# ProPinEZMachBAutoRouteV2c.net
KiCad netlist of a schematic drawn in EAGLE
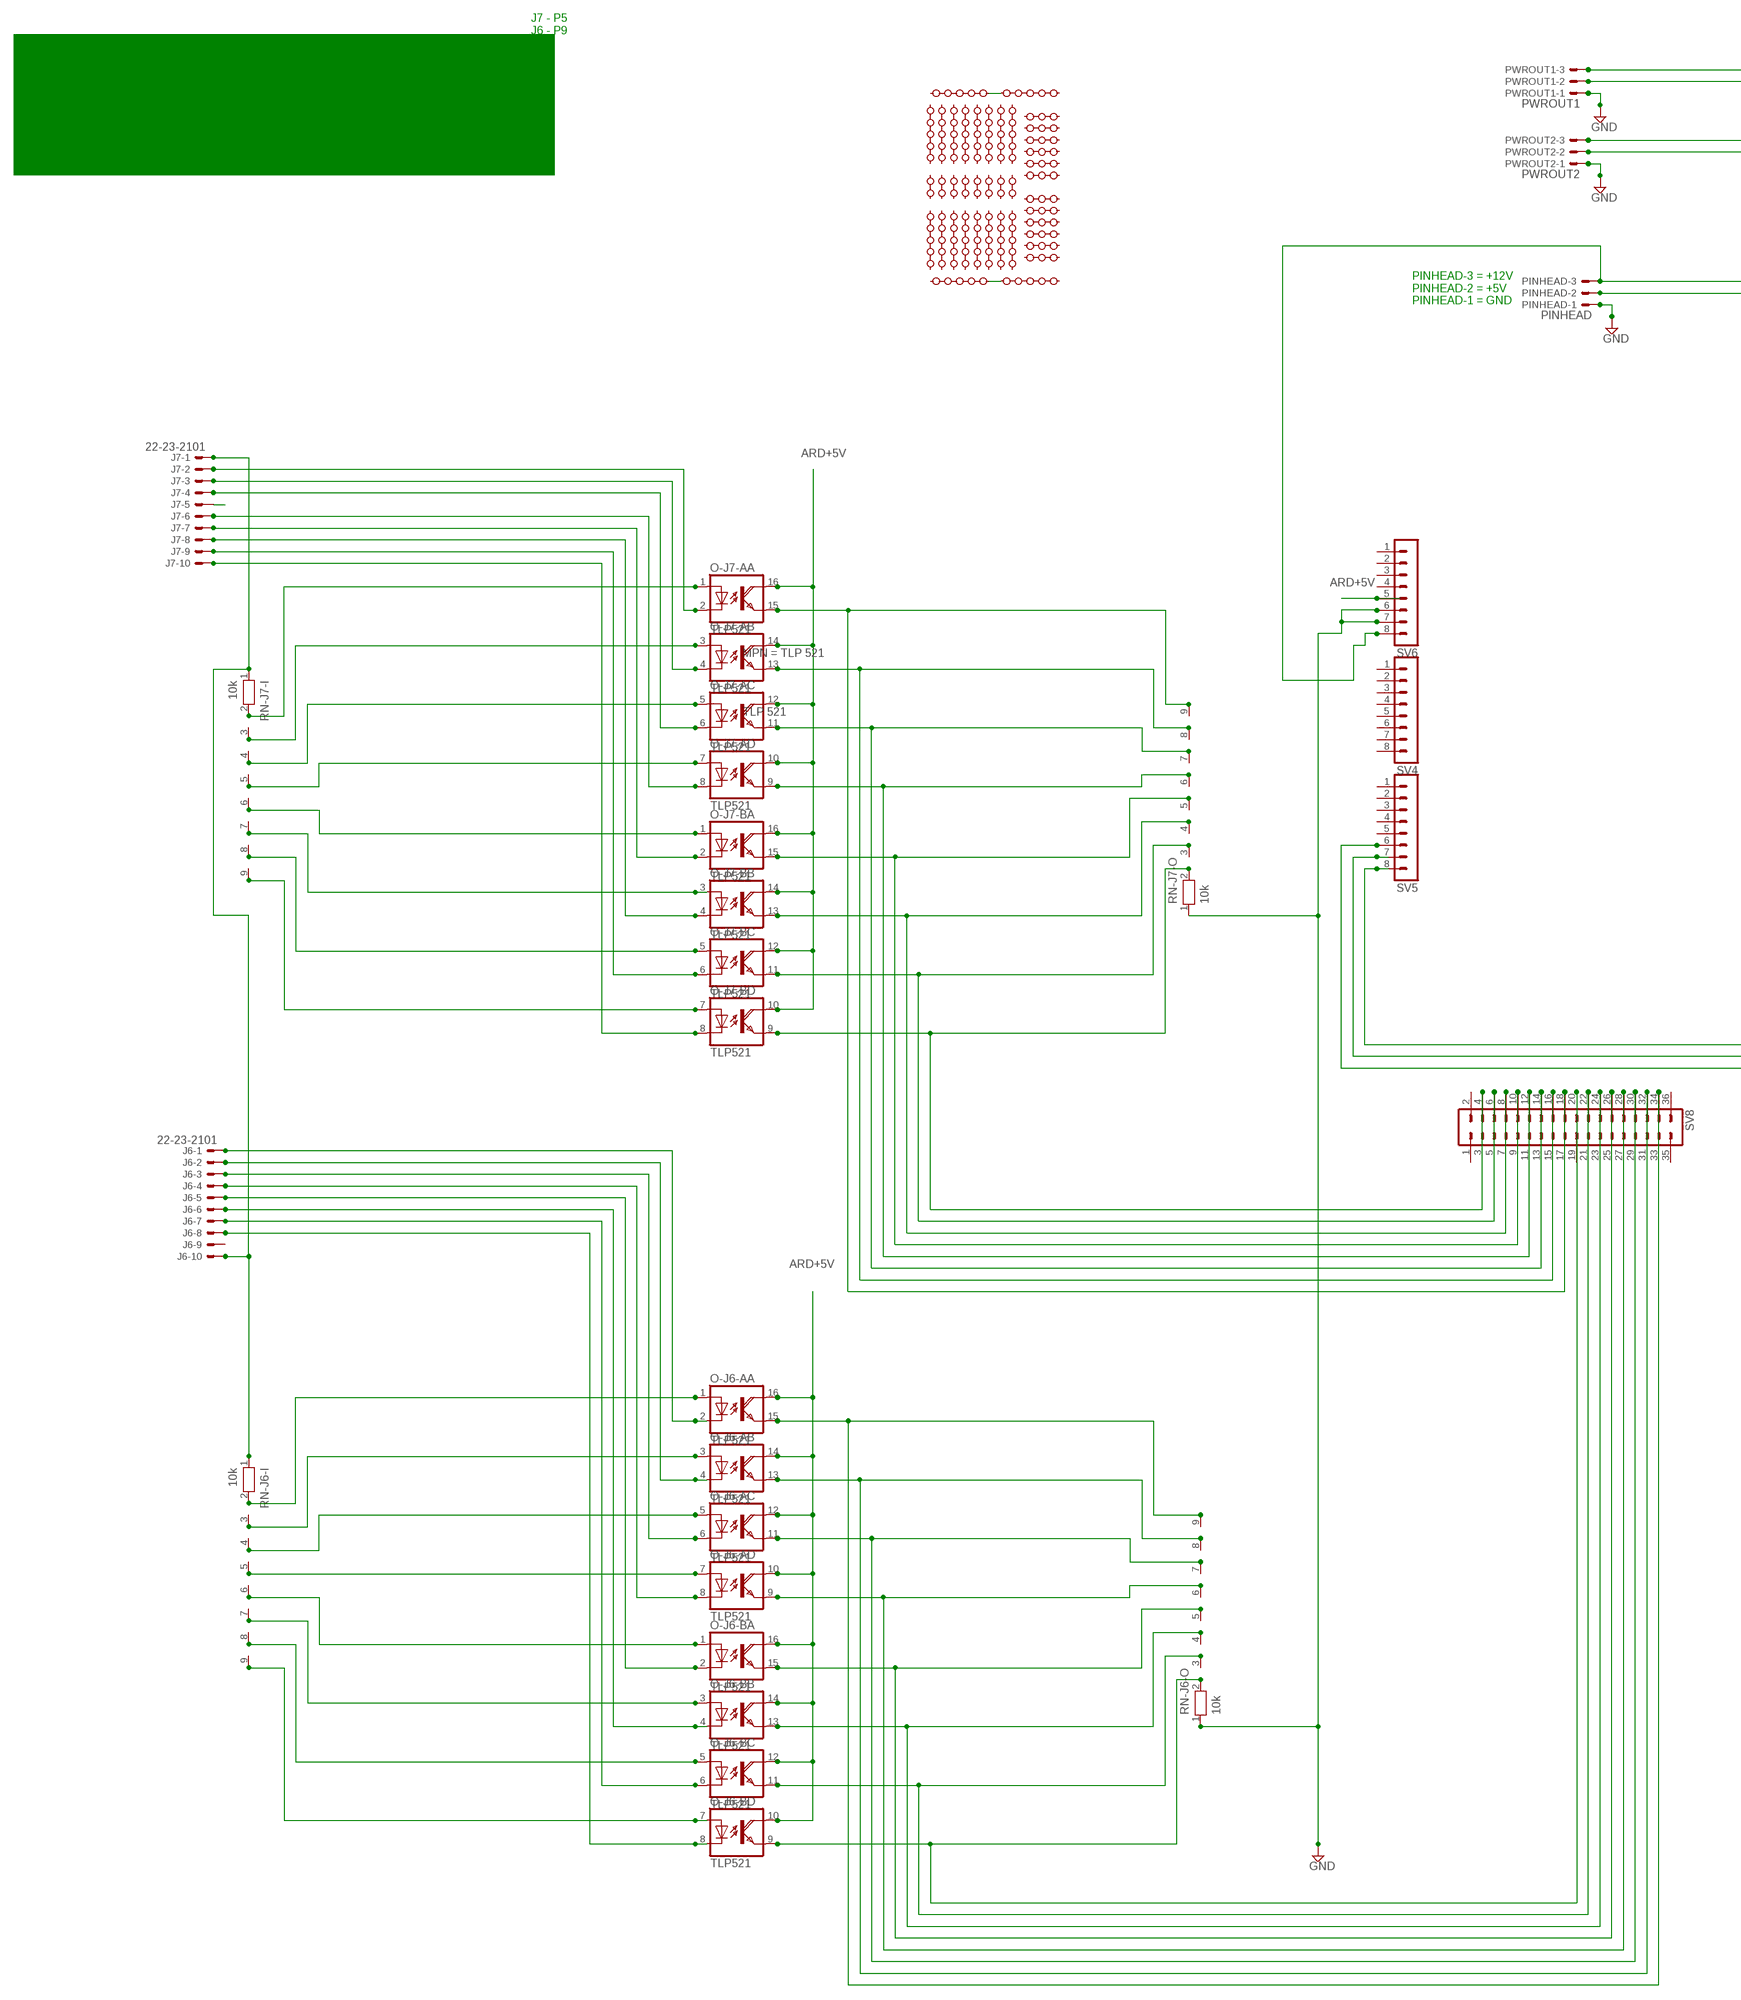
[diagram p0: schematic, sheet 1, part 1 of 2]
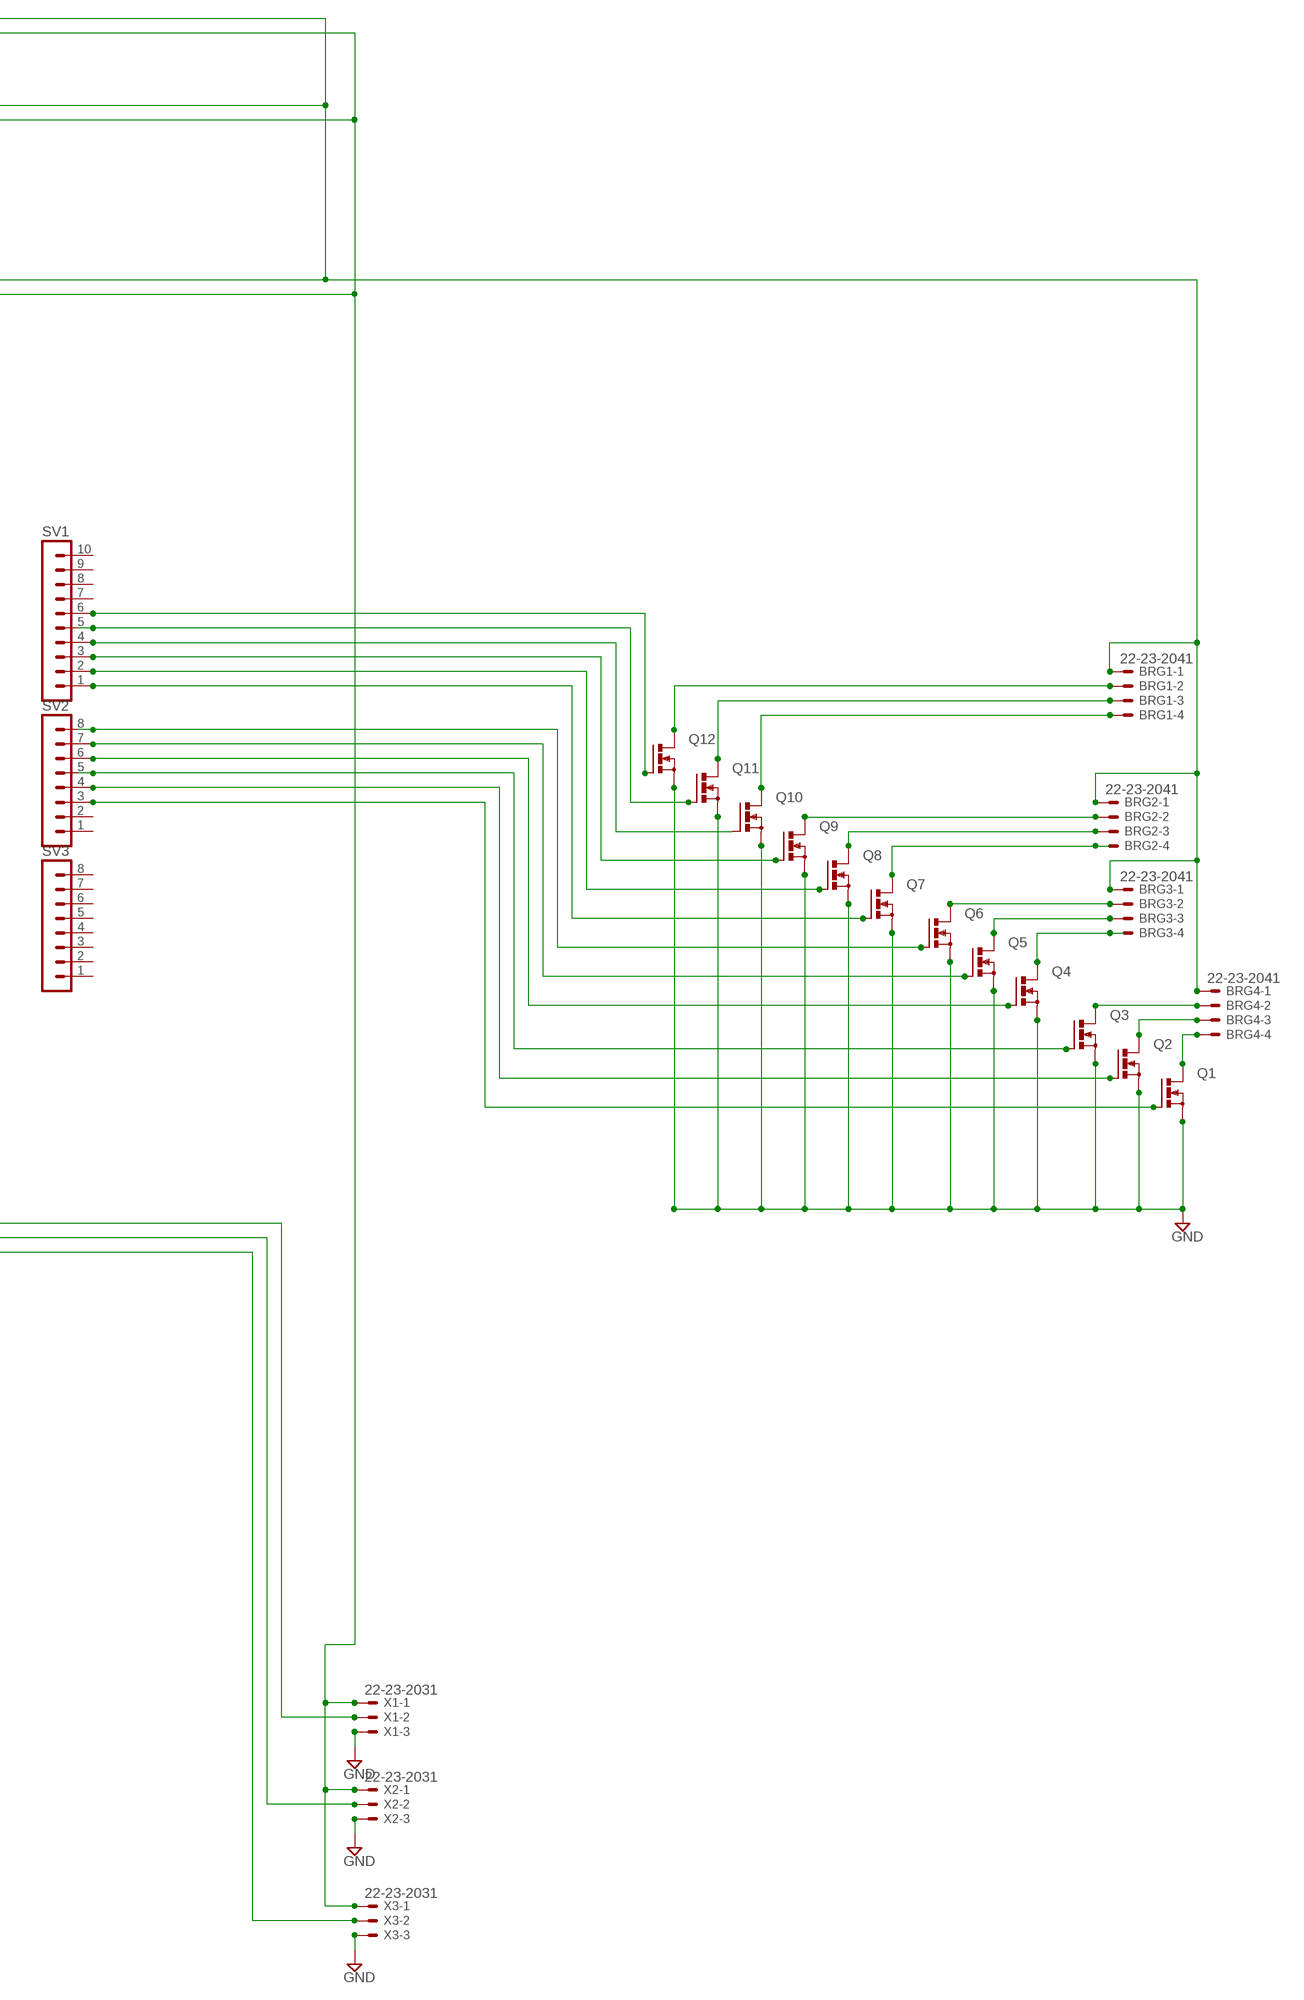
[diagram p1: schematic, sheet 1, part 2 of 2]

(export (version "E")
  (design (tool "Eeschema 10.0.6"))
  (components
    (comp (ref "BRG1")
      (value "22-23-2041")
      (footprint "eagle-import:22-23-2041")
      (fields (field (name "MF") "MOLEX"))
      (libsource (lib "eagle-import") (part "22-23-2041"))
    )
    (comp (ref "BRG2")
      (value "22-23-2041")
      (footprint "eagle-import:22-23-2041")
      (fields (field (name "MF") "MOLEX"))
      (libsource (lib "eagle-import") (part "22-23-2041"))
    )
    (comp (ref "BRG3")
      (value "22-23-2041")
      (footprint "eagle-import:22-23-2041")
      (fields (field (name "MF") "MOLEX"))
      (libsource (lib "eagle-import") (part "22-23-2041"))
    )
    (comp (ref "BRG4")
      (value "22-23-2041")
      (footprint "eagle-import:22-23-2041")
      (fields (field (name "MF") "MOLEX"))
      (libsource (lib "eagle-import") (part "22-23-2041"))
    )
    (comp (ref "J6")
      (value "22-23-2101")
      (footprint "eagle-import:22-23-2101")
      (fields (field (name "MF") "MOLEX"))
      (libsource (lib "eagle-import") (part "22-23-2101"))
    )
    (comp (ref "J7")
      (value "22-23-2101")
      (footprint "eagle-import:22-23-2101")
      (fields (field (name "MF") "MOLEX"))
      (libsource (lib "eagle-import") (part "22-23-2101"))
    )
    (comp (ref "O-J6-A")
      (value "TLP521")
      (footprint "eagle-import:DIL16")
      (fields (field (name "MPN") "TIL 199"))
      (libsource (lib "eagle-import") (part "TIL199"))
    )
    (comp (ref "O-J6-B")
      (value "TLP521")
      (footprint "eagle-import:DIL16")
      (fields (field (name "MPN") "TIL 199"))
      (libsource (lib "eagle-import") (part "TIL199"))
    )
    (comp (ref "O-J7-A")
      (value "TLP521")
      (footprint "eagle-import:DIL16")
      (fields (field (name "MPN") "TIL 199") (field (name "MPN_1") "TLP 521"))
      (libsource (lib "eagle-import") (part "TIL199"))
    )
    (comp (ref "O-J7-B")
      (value "TLP521")
      (footprint "eagle-import:DIL16")
      (fields (field (name "MPN") "TIL 199"))
      (libsource (lib "eagle-import") (part "TIL199"))
    )
    (comp (ref "P1")
      (value "PADSTRIP5-HA")
      (footprint "eagle-import:PADSTRIP-5H")
      (libsource (lib "eagle-import") (part "PADSTRIP5-HA"))
    )
    (comp (ref "P2")
      (value "PADSTRIP5-HA")
      (footprint "eagle-import:PADSTRIP-5H")
      (libsource (lib "eagle-import") (part "PADSTRIP5-HA"))
    )
    (comp (ref "P3")
      (value "PADSTRIP5-HA")
      (footprint "eagle-import:PADSTRIP-5H")
      (libsource (lib "eagle-import") (part "PADSTRIP5-HA"))
    )
    (comp (ref "P4")
      (value "PADSTRIP5-HA")
      (footprint "eagle-import:PADSTRIP-5H")
      (libsource (lib "eagle-import") (part "PADSTRIP5-HA"))
    )
    (comp (ref "P5")
      (value "PADSTRIP5-HA")
      (footprint "eagle-import:PADSTRIP-5H")
      (libsource (lib "eagle-import") (part "PADSTRIP5-HA"))
    )
    (comp (ref "P6")
      (value "PADSTRIP5-HA")
      (footprint "eagle-import:PADSTRIP-5H")
      (libsource (lib "eagle-import") (part "PADSTRIP5-HA"))
    )
    (comp (ref "P7")
      (value "PADSTRIP5-HA")
      (footprint "eagle-import:PADSTRIP-5H")
      (libsource (lib "eagle-import") (part "PADSTRIP5-HA"))
    )
    (comp (ref "P8")
      (value "PADSTRIP5-HA")
      (footprint "eagle-import:PADSTRIP-5H")
      (libsource (lib "eagle-import") (part "PADSTRIP5-HA"))
    )
    (comp (ref "P9")
      (value "PADSTRIP5-HA")
      (footprint "eagle-import:PADSTRIP-5H")
      (libsource (lib "eagle-import") (part "PADSTRIP5-HA"))
    )
    (comp (ref "P10")
      (value "PADSTRIP5-HA")
      (footprint "eagle-import:PADSTRIP-5H")
      (libsource (lib "eagle-import") (part "PADSTRIP5-HA"))
    )
    (comp (ref "P11")
      (value "PADSTRIP5-HA")
      (footprint "eagle-import:PADSTRIP-5H")
      (libsource (lib "eagle-import") (part "PADSTRIP5-HA"))
    )
    (comp (ref "P12")
      (value "PADSTRIP5-HA")
      (footprint "eagle-import:PADSTRIP-5H")
      (libsource (lib "eagle-import") (part "PADSTRIP5-HA"))
    )
    (comp (ref "P13")
      (value "PADSTRIP5-HA")
      (footprint "eagle-import:PADSTRIP-5H")
      (libsource (lib "eagle-import") (part "PADSTRIP5-HA"))
    )
    (comp (ref "P14")
      (value "PADSTRIP5-HA")
      (footprint "eagle-import:PADSTRIP-5H")
      (libsource (lib "eagle-import") (part "PADSTRIP5-HA"))
    )
    (comp (ref "P15")
      (value "PADSTRIP5-HA")
      (footprint "eagle-import:PADSTRIP-5H")
      (libsource (lib "eagle-import") (part "PADSTRIP5-HA"))
    )
    (comp (ref "P16")
      (value "PADSTRIP5-HA")
      (footprint "eagle-import:PADSTRIP-5H")
      (libsource (lib "eagle-import") (part "PADSTRIP5-HA"))
    )
    (comp (ref "P17")
      (value "PADSTRIP5-HB")
      (footprint "eagle-import:PADSTRIP-5HC")
      (libsource (lib "eagle-import") (part "PADSTRIP5-HB"))
    )
    (comp (ref "P18")
      (value "PADSTRIP5-HB")
      (footprint "eagle-import:PADSTRIP-5HC")
      (libsource (lib "eagle-import") (part "PADSTRIP5-HB"))
    )
    (comp (ref "P19")
      (value "PADSTRIP5-HB")
      (footprint "eagle-import:PADSTRIP-5HC")
      (libsource (lib "eagle-import") (part "PADSTRIP5-HB"))
    )
    (comp (ref "P20")
      (value "PADSTRIP5-HB")
      (footprint "eagle-import:PADSTRIP-5HC")
      (libsource (lib "eagle-import") (part "PADSTRIP5-HB"))
    )
    (comp (ref "PINHEAD")
      (value "PINHEAD")
      (footprint "eagle-import:22-23-2031")
      (fields (field (name "MF") "MOLEX") (field (name "MPN") "22-23-2031"))
      (libsource (lib "eagle-import") (part "22-23-2031"))
    )
    (comp (ref "PR1")
      (value "PADSTRIP3-H")
      (footprint "eagle-import:PADSTRIP-3H")
      (libsource (lib "eagle-import") (part "PADSTRIP3-H"))
    )
    (comp (ref "PR2")
      (value "PADSTRIP3-H")
      (footprint "eagle-import:PADSTRIP-3H")
      (libsource (lib "eagle-import") (part "PADSTRIP3-H"))
    )
    (comp (ref "PR3")
      (value "PADSTRIP3-H")
      (footprint "eagle-import:PADSTRIP-3H")
      (libsource (lib "eagle-import") (part "PADSTRIP3-H"))
    )
    (comp (ref "PR4")
      (value "PADSTRIP3-H")
      (footprint "eagle-import:PADSTRIP-3H")
      (libsource (lib "eagle-import") (part "PADSTRIP3-H"))
    )
    (comp (ref "PR5")
      (value "PADSTRIP3-H")
      (footprint "eagle-import:PADSTRIP-3H")
      (libsource (lib "eagle-import") (part "PADSTRIP3-H"))
    )
    (comp (ref "PR6")
      (value "PADSTRIP3-H")
      (footprint "eagle-import:PADSTRIP-3H")
      (libsource (lib "eagle-import") (part "PADSTRIP3-H"))
    )
    (comp (ref "PR7")
      (value "PADSTRIP3-H")
      (footprint "eagle-import:PADSTRIP-3H")
      (libsource (lib "eagle-import") (part "PADSTRIP3-H"))
    )
    (comp (ref "PR8")
      (value "PADSTRIP3-H")
      (footprint "eagle-import:PADSTRIP-3H")
      (libsource (lib "eagle-import") (part "PADSTRIP3-H"))
    )
    (comp (ref "PR9")
      (value "PADSTRIP3-H")
      (footprint "eagle-import:PADSTRIP-3H")
      (libsource (lib "eagle-import") (part "PADSTRIP3-H"))
    )
    (comp (ref "PR10")
      (value "PADSTRIP3-H")
      (footprint "eagle-import:PADSTRIP-3H")
      (libsource (lib "eagle-import") (part "PADSTRIP3-H"))
    )
    (comp (ref "PR13")
      (value "PADSTRIP2-H")
      (footprint "eagle-import:PADSTRIP-2H")
      (libsource (lib "eagle-import") (part "PADSTRIP2-H"))
    )
    (comp (ref "PR14")
      (value "PADSTRIP2-H")
      (footprint "eagle-import:PADSTRIP-2H")
      (libsource (lib "eagle-import") (part "PADSTRIP2-H"))
    )
    (comp (ref "PR15")
      (value "PADSTRIP2-H")
      (footprint "eagle-import:PADSTRIP-2H")
      (libsource (lib "eagle-import") (part "PADSTRIP2-H"))
    )
    (comp (ref "PR16")
      (value "PADSTRIP2-H")
      (footprint "eagle-import:PADSTRIP-2H")
      (libsource (lib "eagle-import") (part "PADSTRIP2-H"))
    )
    (comp (ref "PR17")
      (value "PADSTRIP2-H")
      (footprint "eagle-import:PADSTRIP-2H")
      (libsource (lib "eagle-import") (part "PADSTRIP2-H"))
    )
    (comp (ref "PR18")
      (value "PADSTRIP2-H")
      (footprint "eagle-import:PADSTRIP-2H")
      (libsource (lib "eagle-import") (part "PADSTRIP2-H"))
    )
    (comp (ref "PR19")
      (value "PADSTRIP2-H")
      (footprint "eagle-import:PADSTRIP-2H")
      (libsource (lib "eagle-import") (part "PADSTRIP2-H"))
    )
    (comp (ref "PR20")
      (value "PADSTRIP2-H")
      (footprint "eagle-import:PADSTRIP-2H")
      (libsource (lib "eagle-import") (part "PADSTRIP2-H"))
    )
    (comp (ref "PR23")
      (value "PADSTRIP3-H")
      (footprint "eagle-import:PADSTRIP-3H")
      (libsource (lib "eagle-import") (part "PADSTRIP3-H"))
    )
    (comp (ref "PR24")
      (value "PADSTRIP3-H")
      (footprint "eagle-import:PADSTRIP-3H")
      (libsource (lib "eagle-import") (part "PADSTRIP3-H"))
    )
    (comp (ref "PWROUT1")
      (value "PWROUT1")
      (footprint "eagle-import:22-23-2031")
      (fields (field (name "MF") "MOLEX") (field (name "MPN") "22-23-2031"))
      (libsource (lib "eagle-import") (part "22-23-2031"))
    )
    (comp (ref "PWROUT2")
      (value "PWROUT2")
      (footprint "eagle-import:22-23-2031")
      (fields (field (name "MF") "MOLEX") (field (name "MPN") "22-23-2031"))
      (libsource (lib "eagle-import") (part "22-23-2031"))
    )
    (comp (ref "Q1")
      (value "PMOSFET_NTO220BV")
      (footprint "eagle-import:TO220BV")
      (libsource (lib "eagle-import") (part "PMOSFET_NTO220BV"))
    )
    (comp (ref "Q2")
      (value "PMOSFET_NTO220BV")
      (footprint "eagle-import:TO220BV")
      (libsource (lib "eagle-import") (part "PMOSFET_NTO220BV"))
    )
    (comp (ref "Q3")
      (value "PMOSFET_NTO220BV")
      (footprint "eagle-import:TO220BV")
      (libsource (lib "eagle-import") (part "PMOSFET_NTO220BV"))
    )
    (comp (ref "Q4")
      (value "PMOSFET_NTO220BV")
      (footprint "eagle-import:TO220BV")
      (libsource (lib "eagle-import") (part "PMOSFET_NTO220BV"))
    )
    (comp (ref "Q5")
      (value "PMOSFET_NTO220BV")
      (footprint "eagle-import:TO220BV")
      (libsource (lib "eagle-import") (part "PMOSFET_NTO220BV"))
    )
    (comp (ref "Q6")
      (value "PMOSFET_NTO220BV")
      (footprint "eagle-import:TO220BV")
      (libsource (lib "eagle-import") (part "PMOSFET_NTO220BV"))
    )
    (comp (ref "Q7")
      (value "PMOSFET_NTO220BV")
      (footprint "eagle-import:TO220BV")
      (libsource (lib "eagle-import") (part "PMOSFET_NTO220BV"))
    )
    (comp (ref "Q8")
      (value "PMOSFET_NTO220BV")
      (footprint "eagle-import:TO220BV")
      (libsource (lib "eagle-import") (part "PMOSFET_NTO220BV"))
    )
    (comp (ref "Q9")
      (value "PMOSFET_NTO220BV")
      (footprint "eagle-import:TO220BV")
      (libsource (lib "eagle-import") (part "PMOSFET_NTO220BV"))
    )
    (comp (ref "Q10")
      (value "PMOSFET_NTO220BV")
      (footprint "eagle-import:TO220BV")
      (libsource (lib "eagle-import") (part "PMOSFET_NTO220BV"))
    )
    (comp (ref "Q11")
      (value "PMOSFET_NTO220BV")
      (footprint "eagle-import:TO220BV")
      (libsource (lib "eagle-import") (part "PMOSFET_NTO220BV"))
    )
    (comp (ref "Q12")
      (value "PMOSFET_NTO220BV")
      (footprint "eagle-import:TO220BV")
      (libsource (lib "eagle-import") (part "PMOSFET_NTO220BV"))
    )
    (comp (ref "RN-J6-I")
      (value "10k")
      (footprint "eagle-import:RN-9")
      (libsource (lib "eagle-import") (part "RN08"))
    )
    (comp (ref "RN-J6-O")
      (value "10k")
      (footprint "eagle-import:RN-9")
      (libsource (lib "eagle-import") (part "RN08"))
    )
    (comp (ref "RN-J7-I")
      (value "10k")
      (footprint "eagle-import:RN-9")
      (libsource (lib "eagle-import") (part "RN08"))
    )
    (comp (ref "RN-J7-O")
      (value "10k")
      (footprint "eagle-import:RN-9")
      (libsource (lib "eagle-import") (part "RN08"))
    )
    (comp (ref "SV1")
      (value "MA10-1")
      (footprint "eagle-import:MA10-1")
      (libsource (lib "eagle-import") (part "MA10-1"))
    )
    (comp (ref "SV2")
      (value "MA08-1")
      (footprint "eagle-import:MA08-1")
      (libsource (lib "eagle-import") (part "MA08-1"))
    )
    (comp (ref "SV3")
      (value "MA08-1")
      (footprint "eagle-import:MA08-1")
      (libsource (lib "eagle-import") (part "MA08-1"))
    )
    (comp (ref "SV4")
      (value "MA08-1")
      (footprint "eagle-import:MA08-1")
      (libsource (lib "eagle-import") (part "MA08-1"))
    )
    (comp (ref "SV5")
      (value "MA08-1")
      (footprint "eagle-import:MA08-1")
      (libsource (lib "eagle-import") (part "MA08-1"))
    )
    (comp (ref "SV6")
      (value "MA08-1")
      (footprint "eagle-import:MA08-1")
      (libsource (lib "eagle-import") (part "MA08-1"))
    )
    (comp (ref "SV8")
      (value "MA18-2")
      (footprint "eagle-import:MA18-2")
      (libsource (lib "eagle-import") (part "MA18-2"))
    )
    (comp (ref "X1")
      (value "22-23-2031")
      (footprint "eagle-import:22-23-2031")
      (fields (field (name "MF") "MOLEX"))
      (libsource (lib "eagle-import") (part "22-23-2031"))
    )
    (comp (ref "X2")
      (value "22-23-2031")
      (footprint "eagle-import:22-23-2031")
      (fields (field (name "MF") "MOLEX"))
      (libsource (lib "eagle-import") (part "22-23-2031"))
    )
    (comp (ref "X3")
      (value "22-23-2031")
      (footprint "eagle-import:22-23-2031")
      (fields (field (name "MF") "MOLEX"))
      (libsource (lib "eagle-import") (part "22-23-2031"))
    )
  )
  (nets
    (net (code "1") (name "/ARD+5V") (class "Default")
      (node (ref "O-J6-A") (pin "10") (pinfunction "COL_10") (pintype "passive"))
      (node (ref "O-J6-A") (pin "12") (pinfunction "COL_12") (pintype "passive"))
      (node (ref "O-J6-A") (pin "14") (pinfunction "COL_14") (pintype "passive"))
      (node (ref "O-J6-A") (pin "16") (pinfunction "COL_16") (pintype "passive"))
      (node (ref "O-J6-B") (pin "10") (pinfunction "COL_10") (pintype "passive"))
      (node (ref "O-J6-B") (pin "12") (pinfunction "COL_12") (pintype "passive"))
      (node (ref "O-J6-B") (pin "14") (pinfunction "COL_14") (pintype "passive"))
      (node (ref "O-J6-B") (pin "16") (pinfunction "COL_16") (pintype "passive"))
      (node (ref "O-J7-A") (pin "10") (pinfunction "COL_10") (pintype "passive"))
      (node (ref "O-J7-A") (pin "12") (pinfunction "COL_12") (pintype "passive"))
      (node (ref "O-J7-A") (pin "14") (pinfunction "COL_14") (pintype "passive"))
      (node (ref "O-J7-A") (pin "16") (pinfunction "COL_16") (pintype "passive"))
      (node (ref "O-J7-B") (pin "10") (pinfunction "COL_10") (pintype "passive"))
      (node (ref "O-J7-B") (pin "12") (pinfunction "COL_12") (pintype "passive"))
      (node (ref "O-J7-B") (pin "14") (pinfunction "COL_14") (pintype "passive"))
      (node (ref "O-J7-B") (pin "16") (pinfunction "COL_16") (pintype "passive"))
      (node (ref "SV6") (pin "5") (pinfunction "5_5") (pintype "passive"))
    )
    (net (code "2") (name "GND") (class "Default")
      (node (ref "PINHEAD") (pin "1") (pinfunction "S_1") (pintype "passive"))
      (node (ref "PWROUT1") (pin "1") (pinfunction "S_1") (pintype "passive"))
      (node (ref "PWROUT2") (pin "1") (pinfunction "S_1") (pintype "passive"))
      (node (ref "Q1") (pin "S") (pinfunction "S_S") (pintype "passive"))
      (node (ref "Q10") (pin "S") (pinfunction "S_S") (pintype "passive"))
      (node (ref "Q11") (pin "S") (pinfunction "S_S") (pintype "passive"))
      (node (ref "Q12") (pin "S") (pinfunction "S_S") (pintype "passive"))
      (node (ref "Q2") (pin "S") (pinfunction "S_S") (pintype "passive"))
      (node (ref "Q3") (pin "S") (pinfunction "S_S") (pintype "passive"))
      (node (ref "Q4") (pin "S") (pinfunction "S_S") (pintype "passive"))
      (node (ref "Q5") (pin "S") (pinfunction "S_S") (pintype "passive"))
      (node (ref "Q6") (pin "S") (pinfunction "S_S") (pintype "passive"))
      (node (ref "Q7") (pin "S") (pinfunction "S_S") (pintype "passive"))
      (node (ref "Q8") (pin "S") (pinfunction "S_S") (pintype "passive"))
      (node (ref "Q9") (pin "S") (pinfunction "S_S") (pintype "passive"))
      (node (ref "RN-J6-O") (pin "1") (pinfunction "1_1") (pintype "passive"))
      (node (ref "RN-J7-O") (pin "1") (pinfunction "1_1") (pintype "passive"))
      (node (ref "SV6") (pin "6") (pinfunction "6_6") (pintype "passive"))
      (node (ref "SV6") (pin "7") (pinfunction "7_7") (pintype "passive"))
      (node (ref "X1") (pin "3") (pinfunction "S_3") (pintype "passive"))
      (node (ref "X2") (pin "3") (pinfunction "S_3") (pintype "passive"))
      (node (ref "X3") (pin "3") (pinfunction "S_3") (pintype "passive"))
    )
    (net (code "3") (name "Net-(BRG1A-S)") (class "Default")
      (node (ref "BRG1") (pin "1") (pinfunction "S_1") (pintype "passive"))
      (node (ref "BRG2") (pin "1") (pinfunction "S_1") (pintype "passive"))
      (node (ref "BRG3") (pin "1") (pinfunction "S_1") (pintype "passive"))
      (node (ref "BRG4") (pin "1") (pinfunction "S_1") (pintype "passive"))
      (node (ref "PINHEAD") (pin "3") (pinfunction "S_3") (pintype "passive"))
      (node (ref "PWROUT1") (pin "3") (pinfunction "S_3") (pintype "passive"))
      (node (ref "PWROUT2") (pin "3") (pinfunction "S_3") (pintype "passive"))
      (node (ref "SV6") (pin "8") (pinfunction "8_8") (pintype "passive"))
    )
    (net (code "4") (name "Net-(BRG1B-S)") (class "Default")
      (node (ref "BRG1") (pin "2") (pinfunction "S_2") (pintype "passive"))
      (node (ref "Q12") (pin "D") (pinfunction "D_D") (pintype "passive"))
    )
    (net (code "5") (name "Net-(BRG1C-S)") (class "Default")
      (node (ref "BRG1") (pin "3") (pinfunction "S_3") (pintype "passive"))
      (node (ref "Q11") (pin "D") (pinfunction "D_D") (pintype "passive"))
    )
    (net (code "6") (name "Net-(BRG1D-S)") (class "Default")
      (node (ref "BRG1") (pin "4") (pinfunction "S_4") (pintype "passive"))
      (node (ref "Q10") (pin "D") (pinfunction "D_D") (pintype "passive"))
    )
    (net (code "7") (name "Net-(BRG2B-S)") (class "Default")
      (node (ref "BRG2") (pin "2") (pinfunction "S_2") (pintype "passive"))
      (node (ref "Q9") (pin "D") (pinfunction "D_D") (pintype "passive"))
    )
    (net (code "8") (name "Net-(BRG2C-S)") (class "Default")
      (node (ref "BRG2") (pin "3") (pinfunction "S_3") (pintype "passive"))
      (node (ref "Q8") (pin "D") (pinfunction "D_D") (pintype "passive"))
    )
    (net (code "9") (name "Net-(BRG2D-S)") (class "Default")
      (node (ref "BRG2") (pin "4") (pinfunction "S_4") (pintype "passive"))
      (node (ref "Q7") (pin "D") (pinfunction "D_D") (pintype "passive"))
    )
    (net (code "10") (name "Net-(BRG3B-S)") (class "Default")
      (node (ref "BRG3") (pin "2") (pinfunction "S_2") (pintype "passive"))
      (node (ref "Q6") (pin "D") (pinfunction "D_D") (pintype "passive"))
    )
    (net (code "11") (name "Net-(BRG3C-S)") (class "Default")
      (node (ref "BRG3") (pin "3") (pinfunction "S_3") (pintype "passive"))
      (node (ref "Q5") (pin "D") (pinfunction "D_D") (pintype "passive"))
    )
    (net (code "12") (name "Net-(BRG3D-S)") (class "Default")
      (node (ref "BRG3") (pin "4") (pinfunction "S_4") (pintype "passive"))
      (node (ref "Q4") (pin "D") (pinfunction "D_D") (pintype "passive"))
    )
    (net (code "13") (name "Net-(BRG4B-S)") (class "Default")
      (node (ref "BRG4") (pin "2") (pinfunction "S_2") (pintype "passive"))
      (node (ref "Q3") (pin "D") (pinfunction "D_D") (pintype "passive"))
    )
    (net (code "14") (name "Net-(BRG4C-S)") (class "Default")
      (node (ref "BRG4") (pin "3") (pinfunction "S_3") (pintype "passive"))
      (node (ref "Q2") (pin "D") (pinfunction "D_D") (pintype "passive"))
    )
    (net (code "15") (name "Net-(BRG4D-S)") (class "Default")
      (node (ref "BRG4") (pin "4") (pinfunction "S_4") (pintype "passive"))
      (node (ref "Q1") (pin "D") (pinfunction "D_D") (pintype "passive"))
    )
    (net (code "16") (name "Net-(J6A-S)") (class "Default")
      (node (ref "J6") (pin "1") (pinfunction "S_1") (pintype "passive"))
      (node (ref "O-J6-A") (pin "2") (pinfunction "C_2") (pintype "passive"))
    )
    (net (code "17") (name "Net-(J6B-S)") (class "Default")
      (node (ref "J6") (pin "10") (pinfunction "S_10") (pintype "passive"))
      (node (ref "J7") (pin "1") (pinfunction "S_1") (pintype "passive"))
      (node (ref "RN-J6-I") (pin "1") (pinfunction "1_1") (pintype "passive"))
      (node (ref "RN-J7-I") (pin "1") (pinfunction "1_1") (pintype "passive"))
    )
    (net (code "18") (name "Net-(J6C-S)") (class "Default")
      (node (ref "J6") (pin "2") (pinfunction "S_2") (pintype "passive"))
      (node (ref "O-J6-A") (pin "4") (pinfunction "C_4") (pintype "passive"))
    )
    (net (code "19") (name "Net-(J6D-S)") (class "Default")
      (node (ref "J6") (pin "3") (pinfunction "S_3") (pintype "passive"))
      (node (ref "O-J6-A") (pin "6") (pinfunction "C_6") (pintype "passive"))
    )
    (net (code "20") (name "Net-(J6E-S)") (class "Default")
      (node (ref "J6") (pin "4") (pinfunction "S_4") (pintype "passive"))
      (node (ref "O-J6-A") (pin "8") (pinfunction "C_8") (pintype "passive"))
    )
    (net (code "21") (name "Net-(J6F-S)") (class "Default")
      (node (ref "J6") (pin "5") (pinfunction "S_5") (pintype "passive"))
      (node (ref "O-J6-B") (pin "2") (pinfunction "C_2") (pintype "passive"))
    )
    (net (code "22") (name "Net-(J6G-S)") (class "Default")
      (node (ref "J6") (pin "6") (pinfunction "S_6") (pintype "passive"))
      (node (ref "O-J6-B") (pin "4") (pinfunction "C_4") (pintype "passive"))
    )
    (net (code "23") (name "Net-(J6H-S)") (class "Default")
      (node (ref "J6") (pin "7") (pinfunction "S_7") (pintype "passive"))
      (node (ref "O-J6-B") (pin "6") (pinfunction "C_6") (pintype "passive"))
    )
    (net (code "24") (name "Net-(J6I-S)") (class "Default")
      (node (ref "J6") (pin "8") (pinfunction "S_8") (pintype "passive"))
      (node (ref "O-J6-B") (pin "8") (pinfunction "C_8") (pintype "passive"))
    )
    (net (code "25") (name "Net-(J7B-S)") (class "Default")
      (node (ref "J7") (pin "10") (pinfunction "S_10") (pintype "passive"))
      (node (ref "O-J7-B") (pin "8") (pinfunction "C_8") (pintype "passive"))
    )
    (net (code "26") (name "Net-(J7C-S)") (class "Default")
      (node (ref "J7") (pin "2") (pinfunction "S_2") (pintype "passive"))
      (node (ref "O-J7-A") (pin "2") (pinfunction "C_2") (pintype "passive"))
    )
    (net (code "27") (name "Net-(J7D-S)") (class "Default")
      (node (ref "J7") (pin "3") (pinfunction "S_3") (pintype "passive"))
      (node (ref "O-J7-A") (pin "4") (pinfunction "C_4") (pintype "passive"))
    )
    (net (code "28") (name "Net-(J7E-S)") (class "Default")
      (node (ref "J7") (pin "4") (pinfunction "S_4") (pintype "passive"))
      (node (ref "O-J7-A") (pin "6") (pinfunction "C_6") (pintype "passive"))
    )
    (net (code "29") (name "Net-(J7G-S)") (class "Default")
      (node (ref "J7") (pin "6") (pinfunction "S_6") (pintype "passive"))
      (node (ref "O-J7-A") (pin "8") (pinfunction "C_8") (pintype "passive"))
    )
    (net (code "30") (name "Net-(J7H-S)") (class "Default")
      (node (ref "J7") (pin "7") (pinfunction "S_7") (pintype "passive"))
      (node (ref "O-J7-B") (pin "2") (pinfunction "C_2") (pintype "passive"))
    )
    (net (code "31") (name "Net-(J7I-S)") (class "Default")
      (node (ref "J7") (pin "8") (pinfunction "S_8") (pintype "passive"))
      (node (ref "O-J7-B") (pin "4") (pinfunction "C_4") (pintype "passive"))
    )
    (net (code "32") (name "Net-(J7J-S)") (class "Default")
      (node (ref "J7") (pin "9") (pinfunction "S_9") (pintype "passive"))
      (node (ref "O-J7-B") (pin "6") (pinfunction "C_6") (pintype "passive"))
    )
    (net (code "33") (name "Net-(O-J6-AA-A)") (class "Default")
      (node (ref "O-J6-A") (pin "1") (pinfunction "A_1") (pintype "passive"))
      (node (ref "RN-J6-I") (pin "2") (pinfunction "2_2") (pintype "passive"))
    )
    (net (code "34") (name "Net-(O-J6-AA-EMI)") (class "Default")
      (node (ref "O-J6-A") (pin "15") (pinfunction "EMI_15") (pintype "passive"))
      (node (ref "RN-J6-O") (pin "9") (pinfunction "9_9") (pintype "passive"))
      (node (ref "SV8") (pin "34") (pinfunction "34_34") (pintype "passive"))
    )
    (net (code "35") (name "Net-(O-J6-AB-A)") (class "Default")
      (node (ref "O-J6-A") (pin "3") (pinfunction "A_3") (pintype "passive"))
      (node (ref "RN-J6-I") (pin "3") (pinfunction "3_3") (pintype "passive"))
    )
    (net (code "36") (name "Net-(O-J6-AB-EMI)") (class "Default")
      (node (ref "O-J6-A") (pin "13") (pinfunction "EMI_13") (pintype "passive"))
      (node (ref "RN-J6-O") (pin "8") (pinfunction "8_8") (pintype "passive"))
      (node (ref "SV8") (pin "32") (pinfunction "32_32") (pintype "passive"))
    )
    (net (code "37") (name "Net-(O-J6-AC-A)") (class "Default")
      (node (ref "O-J6-A") (pin "5") (pinfunction "A_5") (pintype "passive"))
      (node (ref "RN-J6-I") (pin "4") (pinfunction "4_4") (pintype "passive"))
    )
    (net (code "38") (name "Net-(O-J6-AC-EMI)") (class "Default")
      (node (ref "O-J6-A") (pin "11") (pinfunction "EMI_11") (pintype "passive"))
      (node (ref "RN-J6-O") (pin "7") (pinfunction "7_7") (pintype "passive"))
      (node (ref "SV8") (pin "30") (pinfunction "30_30") (pintype "passive"))
    )
    (net (code "39") (name "Net-(O-J6-AD-A)") (class "Default")
      (node (ref "O-J6-A") (pin "7") (pinfunction "A_7") (pintype "passive"))
      (node (ref "RN-J6-I") (pin "5") (pinfunction "5_5") (pintype "passive"))
    )
    (net (code "40") (name "Net-(O-J6-AD-EMI)") (class "Default")
      (node (ref "O-J6-A") (pin "9") (pinfunction "EMI_9") (pintype "passive"))
      (node (ref "RN-J6-O") (pin "6") (pinfunction "6_6") (pintype "passive"))
      (node (ref "SV8") (pin "28") (pinfunction "28_28") (pintype "passive"))
    )
    (net (code "41") (name "Net-(O-J6-BA-A)") (class "Default")
      (node (ref "O-J6-B") (pin "1") (pinfunction "A_1") (pintype "passive"))
      (node (ref "RN-J6-I") (pin "6") (pinfunction "6_6") (pintype "passive"))
    )
    (net (code "42") (name "Net-(O-J6-BA-EMI)") (class "Default")
      (node (ref "O-J6-B") (pin "15") (pinfunction "EMI_15") (pintype "passive"))
      (node (ref "RN-J6-O") (pin "5") (pinfunction "5_5") (pintype "passive"))
      (node (ref "SV8") (pin "26") (pinfunction "26_26") (pintype "passive"))
    )
    (net (code "43") (name "Net-(O-J6-BB-A)") (class "Default")
      (node (ref "O-J6-B") (pin "3") (pinfunction "A_3") (pintype "passive"))
      (node (ref "RN-J6-I") (pin "7") (pinfunction "7_7") (pintype "passive"))
    )
    (net (code "44") (name "Net-(O-J6-BB-EMI)") (class "Default")
      (node (ref "O-J6-B") (pin "13") (pinfunction "EMI_13") (pintype "passive"))
      (node (ref "RN-J6-O") (pin "4") (pinfunction "4_4") (pintype "passive"))
      (node (ref "SV8") (pin "24") (pinfunction "24_24") (pintype "passive"))
    )
    (net (code "45") (name "Net-(O-J6-BC-A)") (class "Default")
      (node (ref "O-J6-B") (pin "5") (pinfunction "A_5") (pintype "passive"))
      (node (ref "RN-J6-I") (pin "8") (pinfunction "8_8") (pintype "passive"))
    )
    (net (code "46") (name "Net-(O-J6-BC-EMI)") (class "Default")
      (node (ref "O-J6-B") (pin "11") (pinfunction "EMI_11") (pintype "passive"))
      (node (ref "RN-J6-O") (pin "3") (pinfunction "3_3") (pintype "passive"))
      (node (ref "SV8") (pin "22") (pinfunction "22_22") (pintype "passive"))
    )
    (net (code "47") (name "Net-(O-J6-BD-A)") (class "Default")
      (node (ref "O-J6-B") (pin "7") (pinfunction "A_7") (pintype "passive"))
      (node (ref "RN-J6-I") (pin "9") (pinfunction "9_9") (pintype "passive"))
    )
    (net (code "48") (name "Net-(O-J6-BD-EMI)") (class "Default")
      (node (ref "O-J6-B") (pin "9") (pinfunction "EMI_9") (pintype "passive"))
      (node (ref "RN-J6-O") (pin "2") (pinfunction "2_2") (pintype "passive"))
      (node (ref "SV8") (pin "20") (pinfunction "20_20") (pintype "passive"))
    )
    (net (code "49") (name "Net-(O-J7-AA-A)") (class "Default")
      (node (ref "O-J7-A") (pin "1") (pinfunction "A_1") (pintype "passive"))
      (node (ref "RN-J7-I") (pin "2") (pinfunction "2_2") (pintype "passive"))
    )
    (net (code "50") (name "Net-(O-J7-AA-EMI)") (class "Default")
      (node (ref "O-J7-A") (pin "15") (pinfunction "EMI_15") (pintype "passive"))
      (node (ref "RN-J7-O") (pin "9") (pinfunction "9_9") (pintype "passive"))
      (node (ref "SV8") (pin "18") (pinfunction "18_18") (pintype "passive"))
    )
    (net (code "51") (name "Net-(O-J7-AB-A)") (class "Default")
      (node (ref "O-J7-A") (pin "3") (pinfunction "A_3") (pintype "passive"))
      (node (ref "RN-J7-I") (pin "3") (pinfunction "3_3") (pintype "passive"))
    )
    (net (code "52") (name "Net-(O-J7-AB-EMI)") (class "Default")
      (node (ref "O-J7-A") (pin "13") (pinfunction "EMI_13") (pintype "passive"))
      (node (ref "RN-J7-O") (pin "8") (pinfunction "8_8") (pintype "passive"))
      (node (ref "SV8") (pin "16") (pinfunction "16_16") (pintype "passive"))
    )
    (net (code "53") (name "Net-(O-J7-AC-A)") (class "Default")
      (node (ref "O-J7-A") (pin "5") (pinfunction "A_5") (pintype "passive"))
      (node (ref "RN-J7-I") (pin "4") (pinfunction "4_4") (pintype "passive"))
    )
    (net (code "54") (name "Net-(O-J7-AC-EMI)") (class "Default")
      (node (ref "O-J7-A") (pin "11") (pinfunction "EMI_11") (pintype "passive"))
      (node (ref "RN-J7-O") (pin "7") (pinfunction "7_7") (pintype "passive"))
      (node (ref "SV8") (pin "14") (pinfunction "14_14") (pintype "passive"))
    )
    (net (code "55") (name "Net-(O-J7-AD-A)") (class "Default")
      (node (ref "O-J7-A") (pin "7") (pinfunction "A_7") (pintype "passive"))
      (node (ref "RN-J7-I") (pin "5") (pinfunction "5_5") (pintype "passive"))
    )
    (net (code "56") (name "Net-(O-J7-AD-EMI)") (class "Default")
      (node (ref "O-J7-A") (pin "9") (pinfunction "EMI_9") (pintype "passive"))
      (node (ref "RN-J7-O") (pin "6") (pinfunction "6_6") (pintype "passive"))
      (node (ref "SV8") (pin "12") (pinfunction "12_12") (pintype "passive"))
    )
    (net (code "57") (name "Net-(O-J7-BA-A)") (class "Default")
      (node (ref "O-J7-B") (pin "1") (pinfunction "A_1") (pintype "passive"))
      (node (ref "RN-J7-I") (pin "6") (pinfunction "6_6") (pintype "passive"))
    )
    (net (code "58") (name "Net-(O-J7-BA-EMI)") (class "Default")
      (node (ref "O-J7-B") (pin "15") (pinfunction "EMI_15") (pintype "passive"))
      (node (ref "RN-J7-O") (pin "5") (pinfunction "5_5") (pintype "passive"))
      (node (ref "SV8") (pin "10") (pinfunction "10_10") (pintype "passive"))
    )
    (net (code "59") (name "Net-(O-J7-BB-A)") (class "Default")
      (node (ref "O-J7-B") (pin "3") (pinfunction "A_3") (pintype "passive"))
      (node (ref "RN-J7-I") (pin "7") (pinfunction "7_7") (pintype "passive"))
    )
    (net (code "60") (name "Net-(O-J7-BB-EMI)") (class "Default")
      (node (ref "O-J7-B") (pin "13") (pinfunction "EMI_13") (pintype "passive"))
      (node (ref "RN-J7-O") (pin "4") (pinfunction "4_4") (pintype "passive"))
      (node (ref "SV8") (pin "8") (pinfunction "8_8") (pintype "passive"))
    )
    (net (code "61") (name "Net-(O-J7-BC-A)") (class "Default")
      (node (ref "O-J7-B") (pin "5") (pinfunction "A_5") (pintype "passive"))
      (node (ref "RN-J7-I") (pin "8") (pinfunction "8_8") (pintype "passive"))
    )
    (net (code "62") (name "Net-(O-J7-BC-EMI)") (class "Default")
      (node (ref "O-J7-B") (pin "11") (pinfunction "EMI_11") (pintype "passive"))
      (node (ref "RN-J7-O") (pin "3") (pinfunction "3_3") (pintype "passive"))
      (node (ref "SV8") (pin "6") (pinfunction "6_6") (pintype "passive"))
    )
    (net (code "63") (name "Net-(O-J7-BD-A)") (class "Default")
      (node (ref "O-J7-B") (pin "7") (pinfunction "A_7") (pintype "passive"))
      (node (ref "RN-J7-I") (pin "9") (pinfunction "9_9") (pintype "passive"))
    )
    (net (code "64") (name "Net-(O-J7-BD-EMI)") (class "Default")
      (node (ref "O-J7-B") (pin "9") (pinfunction "EMI_9") (pintype "passive"))
      (node (ref "RN-J7-O") (pin "2") (pinfunction "2_2") (pintype "passive"))
      (node (ref "SV8") (pin "4") (pinfunction "4_4") (pintype "passive"))
    )
    (net (code "65") (name "Net-(P17-Pad5)") (class "Default")
      (node (ref "P17") (pin "5") (pinfunction "5_5") (pintype "bidirectional"))
      (node (ref "P18") (pin "5") (pinfunction "5_5") (pintype "bidirectional"))
    )
    (net (code "66") (name "Net-(P19-Pad5)") (class "Default")
      (node (ref "P19") (pin "5") (pinfunction "5_5") (pintype "bidirectional"))
      (node (ref "P20") (pin "5") (pinfunction "5_5") (pintype "bidirectional"))
    )
    (net (code "67") (name "Net-(PINHEADB-S)") (class "Default")
      (node (ref "PINHEAD") (pin "2") (pinfunction "S_2") (pintype "passive"))
      (node (ref "PWROUT1") (pin "2") (pinfunction "S_2") (pintype "passive"))
      (node (ref "PWROUT2") (pin "2") (pinfunction "S_2") (pintype "passive"))
      (node (ref "X1") (pin "1") (pinfunction "S_1") (pintype "passive"))
      (node (ref "X2") (pin "1") (pinfunction "S_1") (pintype "passive"))
      (node (ref "X3") (pin "1") (pinfunction "S_1") (pintype "passive"))
    )
    (net (code "68") (name "Net-(Q1-PadG)") (class "Default")
      (node (ref "Q1") (pin "G") (pinfunction "G_G") (pintype "passive"))
      (node (ref "SV2") (pin "3") (pinfunction "3_3") (pintype "passive"))
    )
    (net (code "69") (name "Net-(Q2-PadG)") (class "Default")
      (node (ref "Q2") (pin "G") (pinfunction "G_G") (pintype "passive"))
      (node (ref "SV2") (pin "4") (pinfunction "4_4") (pintype "passive"))
    )
    (net (code "70") (name "Net-(Q3-PadG)") (class "Default")
      (node (ref "Q3") (pin "G") (pinfunction "G_G") (pintype "passive"))
      (node (ref "SV2") (pin "5") (pinfunction "5_5") (pintype "passive"))
    )
    (net (code "71") (name "Net-(Q4-PadG)") (class "Default")
      (node (ref "Q4") (pin "G") (pinfunction "G_G") (pintype "passive"))
      (node (ref "SV2") (pin "6") (pinfunction "6_6") (pintype "passive"))
    )
    (net (code "72") (name "Net-(Q5-PadG)") (class "Default")
      (node (ref "Q5") (pin "G") (pinfunction "G_G") (pintype "passive"))
      (node (ref "SV2") (pin "7") (pinfunction "7_7") (pintype "passive"))
    )
    (net (code "73") (name "Net-(Q6-PadG)") (class "Default")
      (node (ref "Q6") (pin "G") (pinfunction "G_G") (pintype "passive"))
      (node (ref "SV2") (pin "8") (pinfunction "8_8") (pintype "passive"))
    )
    (net (code "74") (name "Net-(Q7-PadG)") (class "Default")
      (node (ref "Q7") (pin "G") (pinfunction "G_G") (pintype "passive"))
      (node (ref "SV1") (pin "1") (pinfunction "1_1") (pintype "passive"))
    )
    (net (code "75") (name "Net-(Q8-PadG)") (class "Default")
      (node (ref "Q8") (pin "G") (pinfunction "G_G") (pintype "passive"))
      (node (ref "SV1") (pin "2") (pinfunction "2_2") (pintype "passive"))
    )
    (net (code "76") (name "Net-(Q9-PadG)") (class "Default")
      (node (ref "Q9") (pin "G") (pinfunction "G_G") (pintype "passive"))
      (node (ref "SV1") (pin "3") (pinfunction "3_3") (pintype "passive"))
    )
    (net (code "77") (name "Net-(Q10-PadG)") (class "Default")
      (node (ref "Q10") (pin "G") (pinfunction "G_G") (pintype "passive"))
      (node (ref "SV1") (pin "4") (pinfunction "4_4") (pintype "passive"))
    )
    (net (code "78") (name "Net-(Q11-PadG)") (class "Default")
      (node (ref "Q11") (pin "G") (pinfunction "G_G") (pintype "passive"))
      (node (ref "SV1") (pin "5") (pinfunction "5_5") (pintype "passive"))
    )
    (net (code "79") (name "Net-(Q12-PadG)") (class "Default")
      (node (ref "Q12") (pin "G") (pinfunction "G_G") (pintype "passive"))
      (node (ref "SV1") (pin "6") (pinfunction "6_6") (pintype "passive"))
    )
    (net (code "80") (name "Net-(X1B-S)") (class "Default")
      (node (ref "SV5") (pin "8") (pinfunction "8_8") (pintype "passive"))
      (node (ref "X1") (pin "2") (pinfunction "S_2") (pintype "passive"))
    )
    (net (code "81") (name "Net-(X2B-S)") (class "Default")
      (node (ref "SV5") (pin "7") (pinfunction "7_7") (pintype "passive"))
      (node (ref "X2") (pin "2") (pinfunction "S_2") (pintype "passive"))
    )
    (net (code "82") (name "Net-(X3B-S)") (class "Default")
      (node (ref "SV5") (pin "6") (pinfunction "6_6") (pintype "passive"))
      (node (ref "X3") (pin "2") (pinfunction "S_2") (pintype "passive"))
    )
    (net (code "83") (name "unconnected-(J6J-S-Pad9)") (class "Default")
      (node (ref "J6") (pin "9") (pinfunction "S_9") (pintype "passive"))
    )
    (net (code "84") (name "unconnected-(J7F-S-Pad5)") (class "Default")
      (node (ref "J7") (pin "5") (pinfunction "S_5") (pintype "passive"))
    )
    (net (code "85") (name "unconnected-(P1-Pad1)") (class "Default")
      (node (ref "P1") (pin "1") (pinfunction "1_1") (pintype "bidirectional"))
    )
    (net (code "86") (name "unconnected-(P1-Pad5)") (class "Default")
      (node (ref "P1") (pin "5") (pinfunction "5_5") (pintype "bidirectional"))
    )
    (net (code "87") (name "unconnected-(P2-Pad1)") (class "Default")
      (node (ref "P2") (pin "1") (pinfunction "1_1") (pintype "bidirectional"))
    )
    (net (code "88") (name "unconnected-(P2-Pad5)") (class "Default")
      (node (ref "P2") (pin "5") (pinfunction "5_5") (pintype "bidirectional"))
    )
    (net (code "89") (name "unconnected-(P3-Pad1)") (class "Default")
      (node (ref "P3") (pin "1") (pinfunction "1_1") (pintype "bidirectional"))
    )
    (net (code "90") (name "unconnected-(P3-Pad5)") (class "Default")
      (node (ref "P3") (pin "5") (pinfunction "5_5") (pintype "bidirectional"))
    )
    (net (code "91") (name "unconnected-(P4-Pad1)") (class "Default")
      (node (ref "P4") (pin "1") (pinfunction "1_1") (pintype "bidirectional"))
    )
    (net (code "92") (name "unconnected-(P4-Pad5)") (class "Default")
      (node (ref "P4") (pin "5") (pinfunction "5_5") (pintype "bidirectional"))
    )
    (net (code "93") (name "unconnected-(P5-Pad1)") (class "Default")
      (node (ref "P5") (pin "1") (pinfunction "1_1") (pintype "bidirectional"))
    )
    (net (code "94") (name "unconnected-(P5-Pad5)") (class "Default")
      (node (ref "P5") (pin "5") (pinfunction "5_5") (pintype "bidirectional"))
    )
    (net (code "95") (name "unconnected-(P6-Pad1)") (class "Default")
      (node (ref "P6") (pin "1") (pinfunction "1_1") (pintype "bidirectional"))
    )
    (net (code "96") (name "unconnected-(P6-Pad5)") (class "Default")
      (node (ref "P6") (pin "5") (pinfunction "5_5") (pintype "bidirectional"))
    )
    (net (code "97") (name "unconnected-(P7-Pad1)") (class "Default")
      (node (ref "P7") (pin "1") (pinfunction "1_1") (pintype "bidirectional"))
    )
    (net (code "98") (name "unconnected-(P7-Pad5)") (class "Default")
      (node (ref "P7") (pin "5") (pinfunction "5_5") (pintype "bidirectional"))
    )
    (net (code "99") (name "unconnected-(P8-Pad1)") (class "Default")
      (node (ref "P8") (pin "1") (pinfunction "1_1") (pintype "bidirectional"))
    )
    (net (code "100") (name "unconnected-(P8-Pad5)") (class "Default")
      (node (ref "P8") (pin "5") (pinfunction "5_5") (pintype "bidirectional"))
    )
    (net (code "101") (name "unconnected-(P9-Pad1)") (class "Default")
      (node (ref "P9") (pin "1") (pinfunction "1_1") (pintype "bidirectional"))
    )
    (net (code "102") (name "unconnected-(P9-Pad5)") (class "Default")
      (node (ref "P9") (pin "5") (pinfunction "5_5") (pintype "bidirectional"))
    )
    (net (code "103") (name "unconnected-(P10-Pad1)") (class "Default")
      (node (ref "P10") (pin "1") (pinfunction "1_1") (pintype "bidirectional"))
    )
    (net (code "104") (name "unconnected-(P10-Pad5)") (class "Default")
      (node (ref "P10") (pin "5") (pinfunction "5_5") (pintype "bidirectional"))
    )
    (net (code "105") (name "unconnected-(P11-Pad1)") (class "Default")
      (node (ref "P11") (pin "1") (pinfunction "1_1") (pintype "bidirectional"))
    )
    (net (code "106") (name "unconnected-(P11-Pad5)") (class "Default")
      (node (ref "P11") (pin "5") (pinfunction "5_5") (pintype "bidirectional"))
    )
    (net (code "107") (name "unconnected-(P12-Pad1)") (class "Default")
      (node (ref "P12") (pin "1") (pinfunction "1_1") (pintype "bidirectional"))
    )
    (net (code "108") (name "unconnected-(P12-Pad5)") (class "Default")
      (node (ref "P12") (pin "5") (pinfunction "5_5") (pintype "bidirectional"))
    )
    (net (code "109") (name "unconnected-(P13-Pad1)") (class "Default")
      (node (ref "P13") (pin "1") (pinfunction "1_1") (pintype "bidirectional"))
    )
    (net (code "110") (name "unconnected-(P13-Pad5)") (class "Default")
      (node (ref "P13") (pin "5") (pinfunction "5_5") (pintype "bidirectional"))
    )
    (net (code "111") (name "unconnected-(P14-Pad1)") (class "Default")
      (node (ref "P14") (pin "1") (pinfunction "1_1") (pintype "bidirectional"))
    )
    (net (code "112") (name "unconnected-(P14-Pad5)") (class "Default")
      (node (ref "P14") (pin "5") (pinfunction "5_5") (pintype "bidirectional"))
    )
    (net (code "113") (name "unconnected-(P15-Pad1)") (class "Default")
      (node (ref "P15") (pin "1") (pinfunction "1_1") (pintype "bidirectional"))
    )
    (net (code "114") (name "unconnected-(P15-Pad5)") (class "Default")
      (node (ref "P15") (pin "5") (pinfunction "5_5") (pintype "bidirectional"))
    )
    (net (code "115") (name "unconnected-(P16-Pad1)") (class "Default")
      (node (ref "P16") (pin "1") (pinfunction "1_1") (pintype "bidirectional"))
    )
    (net (code "116") (name "unconnected-(P16-Pad5)") (class "Default")
      (node (ref "P16") (pin "5") (pinfunction "5_5") (pintype "bidirectional"))
    )
    (net (code "117") (name "unconnected-(P17-Pad1)") (class "Default")
      (node (ref "P17") (pin "1") (pinfunction "1_1") (pintype "bidirectional"))
    )
    (net (code "118") (name "unconnected-(P18-Pad1)") (class "Default")
      (node (ref "P18") (pin "1") (pinfunction "1_1") (pintype "bidirectional"))
    )
    (net (code "119") (name "unconnected-(P19-Pad1)") (class "Default")
      (node (ref "P19") (pin "1") (pinfunction "1_1") (pintype "bidirectional"))
    )
    (net (code "120") (name "unconnected-(P20-Pad1)") (class "Default")
      (node (ref "P20") (pin "1") (pinfunction "1_1") (pintype "bidirectional"))
    )
    (net (code "121") (name "unconnected-(PR1-LFT-Pad1)") (class "Default")
      (node (ref "PR1") (pin "1") (pinfunction "LFT_1") (pintype "bidirectional"))
    )
    (net (code "122") (name "unconnected-(PR1-RIT-Pad3)") (class "Default")
      (node (ref "PR1") (pin "3") (pinfunction "RIT_3") (pintype "bidirectional"))
    )
    (net (code "123") (name "unconnected-(PR2-LFT-Pad1)") (class "Default")
      (node (ref "PR2") (pin "1") (pinfunction "LFT_1") (pintype "bidirectional"))
    )
    (net (code "124") (name "unconnected-(PR2-RIT-Pad3)") (class "Default")
      (node (ref "PR2") (pin "3") (pinfunction "RIT_3") (pintype "bidirectional"))
    )
    (net (code "125") (name "unconnected-(PR3-LFT-Pad1)") (class "Default")
      (node (ref "PR3") (pin "1") (pinfunction "LFT_1") (pintype "bidirectional"))
    )
    (net (code "126") (name "unconnected-(PR3-RIT-Pad3)") (class "Default")
      (node (ref "PR3") (pin "3") (pinfunction "RIT_3") (pintype "bidirectional"))
    )
    (net (code "127") (name "unconnected-(PR4-LFT-Pad1)") (class "Default")
      (node (ref "PR4") (pin "1") (pinfunction "LFT_1") (pintype "bidirectional"))
    )
    (net (code "128") (name "unconnected-(PR4-RIT-Pad3)") (class "Default")
      (node (ref "PR4") (pin "3") (pinfunction "RIT_3") (pintype "bidirectional"))
    )
    (net (code "129") (name "unconnected-(PR5-LFT-Pad1)") (class "Default")
      (node (ref "PR5") (pin "1") (pinfunction "LFT_1") (pintype "bidirectional"))
    )
    (net (code "130") (name "unconnected-(PR5-RIT-Pad3)") (class "Default")
      (node (ref "PR5") (pin "3") (pinfunction "RIT_3") (pintype "bidirectional"))
    )
    (net (code "131") (name "unconnected-(PR6-LFT-Pad1)") (class "Default")
      (node (ref "PR6") (pin "1") (pinfunction "LFT_1") (pintype "bidirectional"))
    )
    (net (code "132") (name "unconnected-(PR6-RIT-Pad3)") (class "Default")
      (node (ref "PR6") (pin "3") (pinfunction "RIT_3") (pintype "bidirectional"))
    )
    (net (code "133") (name "unconnected-(PR7-LFT-Pad1)") (class "Default")
      (node (ref "PR7") (pin "1") (pinfunction "LFT_1") (pintype "bidirectional"))
    )
    (net (code "134") (name "unconnected-(PR7-RIT-Pad3)") (class "Default")
      (node (ref "PR7") (pin "3") (pinfunction "RIT_3") (pintype "bidirectional"))
    )
    (net (code "135") (name "unconnected-(PR8-LFT-Pad1)") (class "Default")
      (node (ref "PR8") (pin "1") (pinfunction "LFT_1") (pintype "bidirectional"))
    )
    (net (code "136") (name "unconnected-(PR8-RIT-Pad3)") (class "Default")
      (node (ref "PR8") (pin "3") (pinfunction "RIT_3") (pintype "bidirectional"))
    )
    (net (code "137") (name "unconnected-(PR9-LFT-Pad1)") (class "Default")
      (node (ref "PR9") (pin "1") (pinfunction "LFT_1") (pintype "bidirectional"))
    )
    (net (code "138") (name "unconnected-(PR9-RIT-Pad3)") (class "Default")
      (node (ref "PR9") (pin "3") (pinfunction "RIT_3") (pintype "bidirectional"))
    )
    (net (code "139") (name "unconnected-(PR10-LFT-Pad1)") (class "Default")
      (node (ref "PR10") (pin "1") (pinfunction "LFT_1") (pintype "bidirectional"))
    )
    (net (code "140") (name "unconnected-(PR10-RIT-Pad3)") (class "Default")
      (node (ref "PR10") (pin "3") (pinfunction "RIT_3") (pintype "bidirectional"))
    )
    (net (code "141") (name "unconnected-(PR13-LFT-Pad1)") (class "Default")
      (node (ref "PR13") (pin "1") (pinfunction "LFT_1") (pintype "bidirectional"))
    )
    (net (code "142") (name "unconnected-(PR13-RIT-Pad2)") (class "Default")
      (node (ref "PR13") (pin "2") (pinfunction "RIT_2") (pintype "bidirectional"))
    )
    (net (code "143") (name "unconnected-(PR14-LFT-Pad1)") (class "Default")
      (node (ref "PR14") (pin "1") (pinfunction "LFT_1") (pintype "bidirectional"))
    )
    (net (code "144") (name "unconnected-(PR14-RIT-Pad2)") (class "Default")
      (node (ref "PR14") (pin "2") (pinfunction "RIT_2") (pintype "bidirectional"))
    )
    (net (code "145") (name "unconnected-(PR15-LFT-Pad1)") (class "Default")
      (node (ref "PR15") (pin "1") (pinfunction "LFT_1") (pintype "bidirectional"))
    )
    (net (code "146") (name "unconnected-(PR15-RIT-Pad2)") (class "Default")
      (node (ref "PR15") (pin "2") (pinfunction "RIT_2") (pintype "bidirectional"))
    )
    (net (code "147") (name "unconnected-(PR16-LFT-Pad1)") (class "Default")
      (node (ref "PR16") (pin "1") (pinfunction "LFT_1") (pintype "bidirectional"))
    )
    (net (code "148") (name "unconnected-(PR16-RIT-Pad2)") (class "Default")
      (node (ref "PR16") (pin "2") (pinfunction "RIT_2") (pintype "bidirectional"))
    )
    (net (code "149") (name "unconnected-(PR17-LFT-Pad1)") (class "Default")
      (node (ref "PR17") (pin "1") (pinfunction "LFT_1") (pintype "bidirectional"))
    )
    (net (code "150") (name "unconnected-(PR17-RIT-Pad2)") (class "Default")
      (node (ref "PR17") (pin "2") (pinfunction "RIT_2") (pintype "bidirectional"))
    )
    (net (code "151") (name "unconnected-(PR18-LFT-Pad1)") (class "Default")
      (node (ref "PR18") (pin "1") (pinfunction "LFT_1") (pintype "bidirectional"))
    )
    (net (code "152") (name "unconnected-(PR18-RIT-Pad2)") (class "Default")
      (node (ref "PR18") (pin "2") (pinfunction "RIT_2") (pintype "bidirectional"))
    )
    (net (code "153") (name "unconnected-(PR19-LFT-Pad1)") (class "Default")
      (node (ref "PR19") (pin "1") (pinfunction "LFT_1") (pintype "bidirectional"))
    )
    (net (code "154") (name "unconnected-(PR19-RIT-Pad2)") (class "Default")
      (node (ref "PR19") (pin "2") (pinfunction "RIT_2") (pintype "bidirectional"))
    )
    (net (code "155") (name "unconnected-(PR20-LFT-Pad1)") (class "Default")
      (node (ref "PR20") (pin "1") (pinfunction "LFT_1") (pintype "bidirectional"))
    )
    (net (code "156") (name "unconnected-(PR20-RIT-Pad2)") (class "Default")
      (node (ref "PR20") (pin "2") (pinfunction "RIT_2") (pintype "bidirectional"))
    )
    (net (code "157") (name "unconnected-(PR23-LFT-Pad1)") (class "Default")
      (node (ref "PR23") (pin "1") (pinfunction "LFT_1") (pintype "bidirectional"))
    )
    (net (code "158") (name "unconnected-(PR23-RIT-Pad3)") (class "Default")
      (node (ref "PR23") (pin "3") (pinfunction "RIT_3") (pintype "bidirectional"))
    )
    (net (code "159") (name "unconnected-(PR24-LFT-Pad1)") (class "Default")
      (node (ref "PR24") (pin "1") (pinfunction "LFT_1") (pintype "bidirectional"))
    )
    (net (code "160") (name "unconnected-(PR24-RIT-Pad3)") (class "Default")
      (node (ref "PR24") (pin "3") (pinfunction "RIT_3") (pintype "bidirectional"))
    )
    (net (code "161") (name "unconnected-(SV1-Pad7)") (class "Default")
      (node (ref "SV1") (pin "7") (pinfunction "7_7") (pintype "passive"))
    )
    (net (code "162") (name "unconnected-(SV1-Pad8)") (class "Default")
      (node (ref "SV1") (pin "8") (pinfunction "8_8") (pintype "passive"))
    )
    (net (code "163") (name "unconnected-(SV1-Pad9)") (class "Default")
      (node (ref "SV1") (pin "9") (pinfunction "9_9") (pintype "passive"))
    )
    (net (code "164") (name "unconnected-(SV1-Pad10)") (class "Default")
      (node (ref "SV1") (pin "10") (pinfunction "10_10") (pintype "passive"))
    )
    (net (code "165") (name "unconnected-(SV2-Pad1)") (class "Default")
      (node (ref "SV2") (pin "1") (pinfunction "1_1") (pintype "passive"))
    )
    (net (code "166") (name "unconnected-(SV2-Pad2)") (class "Default")
      (node (ref "SV2") (pin "2") (pinfunction "2_2") (pintype "passive"))
    )
    (net (code "167") (name "unconnected-(SV3-Pad1)") (class "Default")
      (node (ref "SV3") (pin "1") (pinfunction "1_1") (pintype "passive"))
    )
    (net (code "168") (name "unconnected-(SV3-Pad2)") (class "Default")
      (node (ref "SV3") (pin "2") (pinfunction "2_2") (pintype "passive"))
    )
    (net (code "169") (name "unconnected-(SV3-Pad3)") (class "Default")
      (node (ref "SV3") (pin "3") (pinfunction "3_3") (pintype "passive"))
    )
    (net (code "170") (name "unconnected-(SV3-Pad4)") (class "Default")
      (node (ref "SV3") (pin "4") (pinfunction "4_4") (pintype "passive"))
    )
    (net (code "171") (name "unconnected-(SV3-Pad5)") (class "Default")
      (node (ref "SV3") (pin "5") (pinfunction "5_5") (pintype "passive"))
    )
    (net (code "172") (name "unconnected-(SV3-Pad6)") (class "Default")
      (node (ref "SV3") (pin "6") (pinfunction "6_6") (pintype "passive"))
    )
    (net (code "173") (name "unconnected-(SV3-Pad7)") (class "Default")
      (node (ref "SV3") (pin "7") (pinfunction "7_7") (pintype "passive"))
    )
    (net (code "174") (name "unconnected-(SV3-Pad8)") (class "Default")
      (node (ref "SV3") (pin "8") (pinfunction "8_8") (pintype "passive"))
    )
    (net (code "175") (name "unconnected-(SV4-Pad1)") (class "Default")
      (node (ref "SV4") (pin "1") (pinfunction "1_1") (pintype "passive"))
    )
    (net (code "176") (name "unconnected-(SV4-Pad2)") (class "Default")
      (node (ref "SV4") (pin "2") (pinfunction "2_2") (pintype "passive"))
    )
    (net (code "177") (name "unconnected-(SV4-Pad3)") (class "Default")
      (node (ref "SV4") (pin "3") (pinfunction "3_3") (pintype "passive"))
    )
    (net (code "178") (name "unconnected-(SV4-Pad4)") (class "Default")
      (node (ref "SV4") (pin "4") (pinfunction "4_4") (pintype "passive"))
    )
    (net (code "179") (name "unconnected-(SV4-Pad5)") (class "Default")
      (node (ref "SV4") (pin "5") (pinfunction "5_5") (pintype "passive"))
    )
    (net (code "180") (name "unconnected-(SV4-Pad6)") (class "Default")
      (node (ref "SV4") (pin "6") (pinfunction "6_6") (pintype "passive"))
    )
    (net (code "181") (name "unconnected-(SV4-Pad7)") (class "Default")
      (node (ref "SV4") (pin "7") (pinfunction "7_7") (pintype "passive"))
    )
    (net (code "182") (name "unconnected-(SV4-Pad8)") (class "Default")
      (node (ref "SV4") (pin "8") (pinfunction "8_8") (pintype "passive"))
    )
    (net (code "183") (name "unconnected-(SV5-Pad1)") (class "Default")
      (node (ref "SV5") (pin "1") (pinfunction "1_1") (pintype "passive"))
    )
    (net (code "184") (name "unconnected-(SV5-Pad2)") (class "Default")
      (node (ref "SV5") (pin "2") (pinfunction "2_2") (pintype "passive"))
    )
    (net (code "185") (name "unconnected-(SV5-Pad3)") (class "Default")
      (node (ref "SV5") (pin "3") (pinfunction "3_3") (pintype "passive"))
    )
    (net (code "186") (name "unconnected-(SV5-Pad4)") (class "Default")
      (node (ref "SV5") (pin "4") (pinfunction "4_4") (pintype "passive"))
    )
    (net (code "187") (name "unconnected-(SV5-Pad5)") (class "Default")
      (node (ref "SV5") (pin "5") (pinfunction "5_5") (pintype "passive"))
    )
    (net (code "188") (name "unconnected-(SV6-Pad1)") (class "Default")
      (node (ref "SV6") (pin "1") (pinfunction "1_1") (pintype "passive"))
    )
    (net (code "189") (name "unconnected-(SV6-Pad2)") (class "Default")
      (node (ref "SV6") (pin "2") (pinfunction "2_2") (pintype "passive"))
    )
    (net (code "190") (name "unconnected-(SV6-Pad3)") (class "Default")
      (node (ref "SV6") (pin "3") (pinfunction "3_3") (pintype "passive"))
    )
    (net (code "191") (name "unconnected-(SV6-Pad4)") (class "Default")
      (node (ref "SV6") (pin "4") (pinfunction "4_4") (pintype "passive"))
    )
    (net (code "192") (name "unconnected-(SV8-Pad1)") (class "Default")
      (node (ref "SV8") (pin "1") (pinfunction "1_1") (pintype "passive"))
    )
    (net (code "193") (name "unconnected-(SV8-Pad2)") (class "Default")
      (node (ref "SV8") (pin "2") (pinfunction "2_2") (pintype "passive"))
    )
    (net (code "194") (name "unconnected-(SV8-Pad3)") (class "Default")
      (node (ref "SV8") (pin "3") (pinfunction "3_3") (pintype "passive"))
    )
    (net (code "195") (name "unconnected-(SV8-Pad5)") (class "Default")
      (node (ref "SV8") (pin "5") (pinfunction "5_5") (pintype "passive"))
    )
    (net (code "196") (name "unconnected-(SV8-Pad7)") (class "Default")
      (node (ref "SV8") (pin "7") (pinfunction "7_7") (pintype "passive"))
    )
    (net (code "197") (name "unconnected-(SV8-Pad9)") (class "Default")
      (node (ref "SV8") (pin "9") (pinfunction "9_9") (pintype "passive"))
    )
    (net (code "198") (name "unconnected-(SV8-Pad11)") (class "Default")
      (node (ref "SV8") (pin "11") (pinfunction "11_11") (pintype "passive"))
    )
    (net (code "199") (name "unconnected-(SV8-Pad13)") (class "Default")
      (node (ref "SV8") (pin "13") (pinfunction "13_13") (pintype "passive"))
    )
    (net (code "200") (name "unconnected-(SV8-Pad15)") (class "Default")
      (node (ref "SV8") (pin "15") (pinfunction "15_15") (pintype "passive"))
    )
    (net (code "201") (name "unconnected-(SV8-Pad17)") (class "Default")
      (node (ref "SV8") (pin "17") (pinfunction "17_17") (pintype "passive"))
    )
    (net (code "202") (name "unconnected-(SV8-Pad19)") (class "Default")
      (node (ref "SV8") (pin "19") (pinfunction "19_19") (pintype "passive"))
    )
    (net (code "203") (name "unconnected-(SV8-Pad21)") (class "Default")
      (node (ref "SV8") (pin "21") (pinfunction "21_21") (pintype "passive"))
    )
    (net (code "204") (name "unconnected-(SV8-Pad23)") (class "Default")
      (node (ref "SV8") (pin "23") (pinfunction "23_23") (pintype "passive"))
    )
    (net (code "205") (name "unconnected-(SV8-Pad25)") (class "Default")
      (node (ref "SV8") (pin "25") (pinfunction "25_25") (pintype "passive"))
    )
    (net (code "206") (name "unconnected-(SV8-Pad27)") (class "Default")
      (node (ref "SV8") (pin "27") (pinfunction "27_27") (pintype "passive"))
    )
    (net (code "207") (name "unconnected-(SV8-Pad29)") (class "Default")
      (node (ref "SV8") (pin "29") (pinfunction "29_29") (pintype "passive"))
    )
    (net (code "208") (name "unconnected-(SV8-Pad31)") (class "Default")
      (node (ref "SV8") (pin "31") (pinfunction "31_31") (pintype "passive"))
    )
    (net (code "209") (name "unconnected-(SV8-Pad33)") (class "Default")
      (node (ref "SV8") (pin "33") (pinfunction "33_33") (pintype "passive"))
    )
    (net (code "210") (name "unconnected-(SV8-Pad35)") (class "Default")
      (node (ref "SV8") (pin "35") (pinfunction "35_35") (pintype "passive"))
    )
    (net (code "211") (name "unconnected-(SV8-Pad36)") (class "Default")
      (node (ref "SV8") (pin "36") (pinfunction "36_36") (pintype "passive"))
    )
  )
)
